# Kit_10_Pin_Inverter.net
KiCad netlist of a schematic drawn in EAGLE
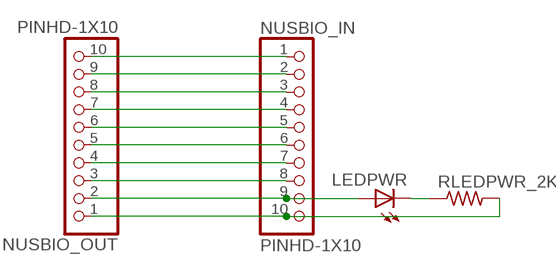
[diagram p0: schematic, sheet 1]

(export (version "E")
  (design (tool "Eeschema 10.0.6"))
  (components
    (comp (ref "LEDPWR")
      (value "LEDCHIPLED_0805")
      (footprint "eagle-import:CHIPLED_0805")
      (libsource (lib "eagle-import") (part "LEDCHIPLED_0805"))
    )
    (comp (ref "NUSBIO_IN")
      (value "PINHD-1X10")
      (footprint "eagle-import:1X10-BIG")
      (libsource (lib "eagle-import") (part "PINHD-1X10"))
    )
    (comp (ref "NUSBIO_OUT")
      (value "PINHD-1X10")
      (footprint "eagle-import:1X10-BIG")
      (libsource (lib "eagle-import") (part "PINHD-1X10"))
    )
    (comp (ref "RLEDPWR_2K")
      (value "R-US_R0805")
      (footprint "eagle-import:R0805")
      (libsource (lib "eagle-import") (part "R-US_R0805"))
    )
  )
  (nets
    (net (code "1") (name "Net-(LEDPWR-PadA)") (class "Default")
      (node (ref "LEDPWR") (pin "A") (pinfunction "A_A") (pintype "passive"))
      (node (ref "NUSBIO_IN") (pin "9") (pinfunction "9_9") (pintype "passive"))
      (node (ref "NUSBIO_OUT") (pin "2") (pinfunction "2_2") (pintype "passive"))
    )
    (net (code "2") (name "Net-(LEDPWR-PadC)") (class "Default")
      (node (ref "LEDPWR") (pin "C") (pinfunction "C_C") (pintype "passive"))
      (node (ref "RLEDPWR_2K") (pin "1") (pinfunction "1_1") (pintype "passive"))
    )
    (net (code "3") (name "Net-(NUSBIO_IN-Pad1)") (class "Default")
      (node (ref "NUSBIO_IN") (pin "1") (pinfunction "1_1") (pintype "passive"))
      (node (ref "NUSBIO_OUT") (pin "10") (pinfunction "10_10") (pintype "passive"))
    )
    (net (code "4") (name "Net-(NUSBIO_IN-Pad2)") (class "Default")
      (node (ref "NUSBIO_IN") (pin "2") (pinfunction "2_2") (pintype "passive"))
      (node (ref "NUSBIO_OUT") (pin "9") (pinfunction "9_9") (pintype "passive"))
    )
    (net (code "5") (name "Net-(NUSBIO_IN-Pad3)") (class "Default")
      (node (ref "NUSBIO_IN") (pin "3") (pinfunction "3_3") (pintype "passive"))
      (node (ref "NUSBIO_OUT") (pin "8") (pinfunction "8_8") (pintype "passive"))
    )
    (net (code "6") (name "Net-(NUSBIO_IN-Pad4)") (class "Default")
      (node (ref "NUSBIO_IN") (pin "4") (pinfunction "4_4") (pintype "passive"))
      (node (ref "NUSBIO_OUT") (pin "7") (pinfunction "7_7") (pintype "passive"))
    )
    (net (code "7") (name "Net-(NUSBIO_IN-Pad5)") (class "Default")
      (node (ref "NUSBIO_IN") (pin "5") (pinfunction "5_5") (pintype "passive"))
      (node (ref "NUSBIO_OUT") (pin "6") (pinfunction "6_6") (pintype "passive"))
    )
    (net (code "8") (name "Net-(NUSBIO_IN-Pad6)") (class "Default")
      (node (ref "NUSBIO_IN") (pin "6") (pinfunction "6_6") (pintype "passive"))
      (node (ref "NUSBIO_OUT") (pin "5") (pinfunction "5_5") (pintype "passive"))
    )
    (net (code "9") (name "Net-(NUSBIO_IN-Pad7)") (class "Default")
      (node (ref "NUSBIO_IN") (pin "7") (pinfunction "7_7") (pintype "passive"))
      (node (ref "NUSBIO_OUT") (pin "4") (pinfunction "4_4") (pintype "passive"))
    )
    (net (code "10") (name "Net-(NUSBIO_IN-Pad8)") (class "Default")
      (node (ref "NUSBIO_IN") (pin "8") (pinfunction "8_8") (pintype "passive"))
      (node (ref "NUSBIO_OUT") (pin "3") (pinfunction "3_3") (pintype "passive"))
    )
    (net (code "11") (name "Net-(NUSBIO_IN-Pad10)") (class "Default")
      (node (ref "NUSBIO_IN") (pin "10") (pinfunction "10_10") (pintype "passive"))
      (node (ref "NUSBIO_OUT") (pin "1") (pinfunction "1_1") (pintype "passive"))
      (node (ref "RLEDPWR_2K") (pin "2") (pinfunction "2_2") (pintype "passive"))
    )
  )
)
